# Sheet1.net
KiCad netlist of a schematic drawn in Altium Designer
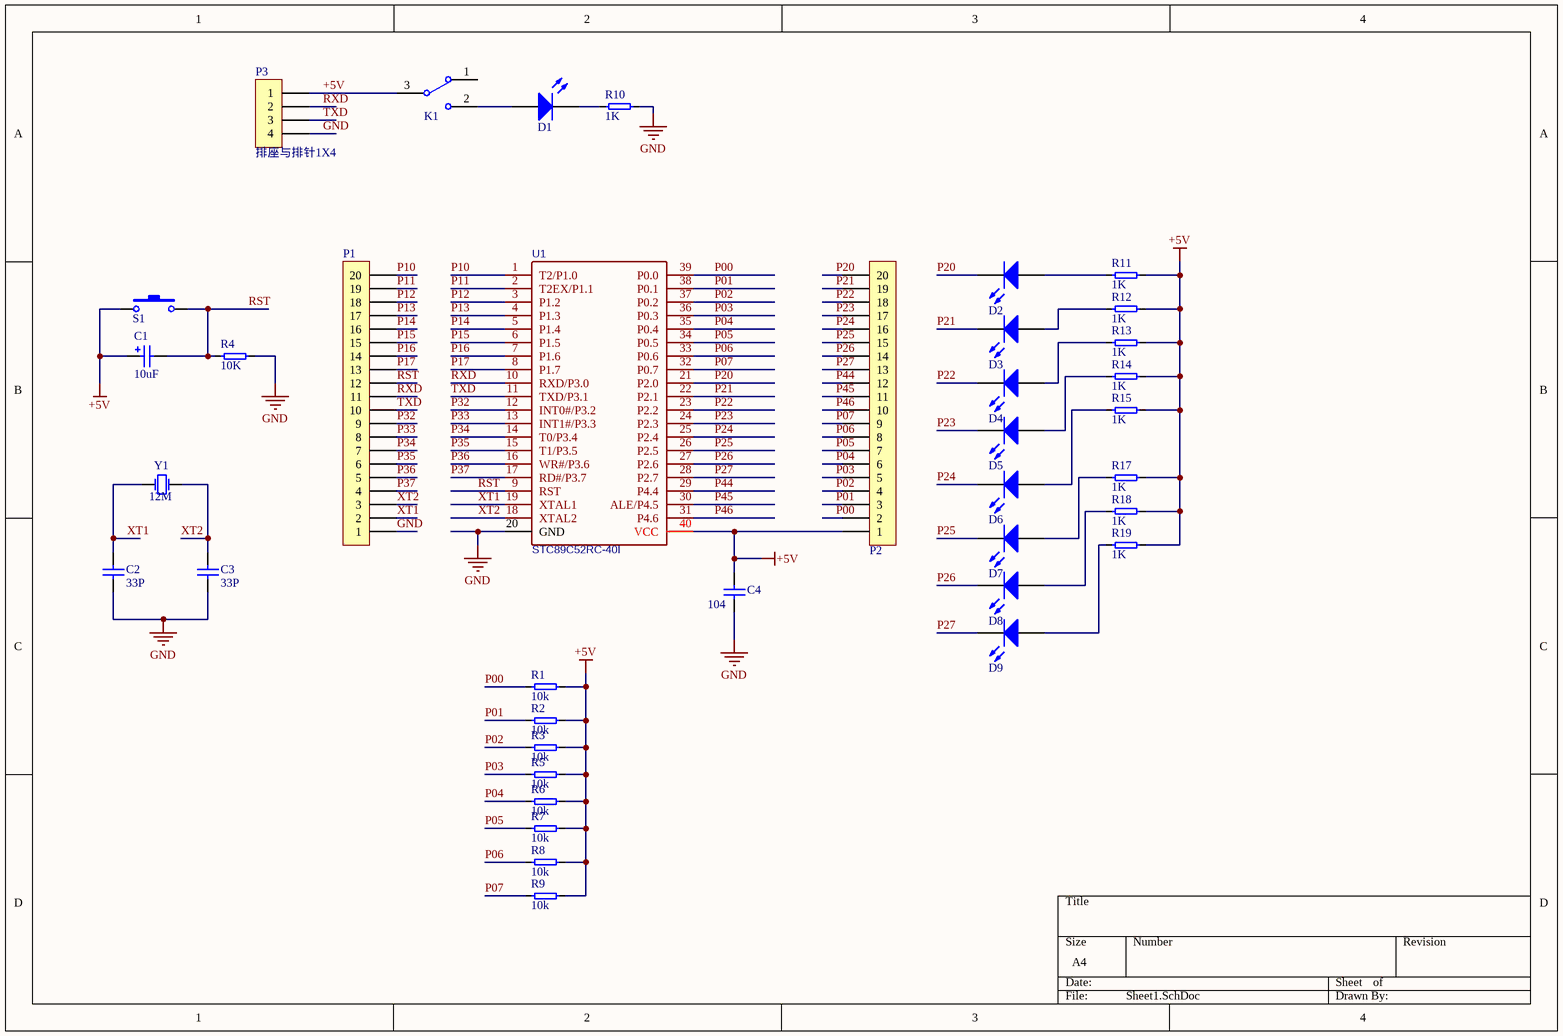
[diagram p0: Sheet1.SchDoc]

(export (version "E")
  (design (tool "Eeschema 10.0.6"))
  (components
    (comp (ref "C1") (value "10uF") (footprint "CAP4*7") (libsource (lib "Csust_B503") (part "电解电容")))
    (comp (ref "C2") (value "33P") (footprint "0805-C") (libsource (lib "Csust_B503") (part "电容")))
    (comp (ref "C3") (value "33P") (footprint "0805-C") (libsource (lib "Csust_B503") (part "电容")))
    (comp (ref "C4") (value "104") (footprint "0805-C") (libsource (lib "Csust_B503") (part "电容")))
    (comp (ref "D1") (value "LED") (footprint "LED-BLUE-0805") (libsource (lib "Csust_B503") (part "LED")))
    (comp (ref "D2") (value "LED") (footprint "LED-BLUE-0805") (libsource (lib "Csust_B503") (part "LED")))
    (comp (ref "D3") (value "LED") (footprint "LED-BLUE-0805") (libsource (lib "Csust_B503") (part "LED")))
    (comp (ref "D4") (value "LED") (footprint "LED-BLUE-0805") (libsource (lib "Csust_B503") (part "LED")))
    (comp (ref "D5") (value "LED") (footprint "LED-BLUE-0805") (libsource (lib "Csust_B503") (part "LED")))
    (comp (ref "D6") (value "LED") (footprint "LED-BLUE-0805") (libsource (lib "Csust_B503") (part "LED")))
    (comp (ref "D7") (value "LED") (footprint "LED-BLUE-0805") (libsource (lib "Csust_B503") (part "LED")))
    (comp (ref "D8") (value "LED") (footprint "LED-BLUE-0805") (libsource (lib "Csust_B503") (part "LED")))
    (comp (ref "D9") (value "LED") (footprint "LED-BLUE-0805") (libsource (lib "Csust_B503") (part "LED")))
    (comp (ref "K1") (value "开关") (footprint "开关(自锁)") (libsource (lib "Csust_B503") (part "开关")))
    (comp (ref "P1") (value "排座与排针1X20") (footprint "Header1X20") (libsource (lib "") (part "排座与排针1X20_1")))
    (comp (ref "P2")
      (value "排座与排针1X20")
      (footprint "Header1X20")
      (libsource (lib "Csust_B503") (part "排座与排针1X20"))
    )
    (comp (ref "P3")
      (value "排座与排针1X4")
      (footprint "Female1X4")
      (libsource (lib "Csust_B503") (part "排座与排针1X4"))
    )
    (comp (ref "R1") (value "10k") (footprint "0805-R") (libsource (lib "Csust_B503") (part "电阻")))
    (comp (ref "R2") (value "10k") (footprint "0805-R") (libsource (lib "Csust_B503") (part "电阻")))
    (comp (ref "R3") (value "10k") (footprint "0805-R") (libsource (lib "Csust_B503") (part "电阻")))
    (comp (ref "R4") (value "10K") (footprint "0805-R") (libsource (lib "Csust_B503") (part "电阻")))
    (comp (ref "R5") (value "10k") (footprint "0805-R") (libsource (lib "Csust_B503") (part "电阻")))
    (comp (ref "R6") (value "10k") (footprint "0805-R") (libsource (lib "Csust_B503") (part "电阻")))
    (comp (ref "R7") (value "10k") (footprint "0805-R") (libsource (lib "Csust_B503") (part "电阻")))
    (comp (ref "R8") (value "10k") (footprint "0805-R") (libsource (lib "Csust_B503") (part "电阻")))
    (comp (ref "R9") (value "10k") (footprint "0805-R") (libsource (lib "Csust_B503") (part "电阻")))
    (comp (ref "R10") (value "1K") (footprint "0805-R") (libsource (lib "Csust_B503") (part "电阻")))
    (comp (ref "R11") (value "1K") (footprint "0805-R") (libsource (lib "Csust_B503") (part "电阻")))
    (comp (ref "R12") (value "1K") (footprint "0805-R") (libsource (lib "Csust_B503") (part "电阻")))
    (comp (ref "R13") (value "1K") (footprint "0805-R") (libsource (lib "Csust_B503") (part "电阻")))
    (comp (ref "R14") (value "1K") (footprint "0805-R") (libsource (lib "Csust_B503") (part "电阻")))
    (comp (ref "R15") (value "1K") (footprint "0805-R") (libsource (lib "Csust_B503") (part "电阻")))
    (comp (ref "R17") (value "1K") (footprint "0805-R") (libsource (lib "Csust_B503") (part "电阻")))
    (comp (ref "R18") (value "1K") (footprint "0805-R") (libsource (lib "Csust_B503") (part "电阻")))
    (comp (ref "R19") (value "1K") (footprint "0805-R") (libsource (lib "Csust_B503") (part "电阻")))
    (comp (ref "S1") (value "按键") (footprint "按键(小)") (libsource (lib "Csust_B503") (part "按键")))
    (comp (ref "U1")
      (value "STC89C52RC-40I")
      (footprint "DIP-40_LS15.24-L52.58-W13.97-H4.83-PITCH2.54")
      (fields (field (name "BOM_SUPPLIER PART") "C14022"))
      (libsource (lib "MUAT") (part "STC89C52RC-40I"))
    )
    (comp (ref "Y1") (value "12M") (footprint "晶振(HC49S型)") (libsource (lib "Csust_B503") (part "晶振")))
  )
  (nets
    (net (code "1") (name "+5V") (class "Default")
      (node (ref "C1") (pin "1") (pinfunction "1_1") (pintype "passive"))
      (node (ref "C4") (pin "2") (pinfunction "2_2") (pintype "power_in"))
      (node (ref "K1") (pin "3") (pinfunction "3_3") (pintype "passive"))
      (node (ref "P2") (pin "1") (pinfunction "1_1") (pintype "passive"))
      (node (ref "P3") (pin "1") (pinfunction "1_1") (pintype "passive"))
      (node (ref "R1") (pin "2") (pinfunction "2_2") (pintype "passive"))
      (node (ref "R11") (pin "2") (pinfunction "2_2") (pintype "passive"))
      (node (ref "R12") (pin "2") (pinfunction "2_2") (pintype "passive"))
      (node (ref "R13") (pin "2") (pinfunction "2_2") (pintype "passive"))
      (node (ref "R14") (pin "2") (pinfunction "2_2") (pintype "passive"))
      (node (ref "R15") (pin "2") (pinfunction "2_2") (pintype "passive"))
      (node (ref "R17") (pin "2") (pinfunction "2_2") (pintype "passive"))
      (node (ref "R18") (pin "2") (pinfunction "2_2") (pintype "passive"))
      (node (ref "R19") (pin "2") (pinfunction "2_2") (pintype "passive"))
      (node (ref "R2") (pin "2") (pinfunction "2_2") (pintype "passive"))
      (node (ref "R3") (pin "2") (pinfunction "2_2") (pintype "passive"))
      (node (ref "R5") (pin "2") (pinfunction "2_2") (pintype "passive"))
      (node (ref "R6") (pin "2") (pinfunction "2_2") (pintype "passive"))
      (node (ref "R7") (pin "2") (pinfunction "2_2") (pintype "passive"))
      (node (ref "R8") (pin "2") (pinfunction "2_2") (pintype "passive"))
      (node (ref "R9") (pin "2") (pinfunction "2_2") (pintype "passive"))
      (node (ref "S1") (pin "1") (pinfunction "1_1") (pintype "passive"))
      (node (ref "U1") (pin "40") (pinfunction "VCC_40") (pintype "passive"))
    )
    (net (code "2") (name "/P00") (class "Default")
      (node (ref "P2") (pin "2") (pinfunction "2_2") (pintype "passive"))
      (node (ref "R1") (pin "1") (pinfunction "1_1") (pintype "passive"))
      (node (ref "U1") (pin "39") (pinfunction "P0.0_39") (pintype "passive"))
    )
    (net (code "3") (name "/P01") (class "Default")
      (node (ref "P2") (pin "3") (pinfunction "3_3") (pintype "passive"))
      (node (ref "R2") (pin "1") (pinfunction "1_1") (pintype "passive"))
      (node (ref "U1") (pin "38") (pinfunction "P0.1_38") (pintype "passive"))
    )
    (net (code "4") (name "/P02") (class "Default")
      (node (ref "P2") (pin "4") (pinfunction "4_4") (pintype "passive"))
      (node (ref "R3") (pin "1") (pinfunction "1_1") (pintype "passive"))
      (node (ref "U1") (pin "37") (pinfunction "P0.2_37") (pintype "passive"))
    )
    (net (code "5") (name "/P03") (class "Default")
      (node (ref "P2") (pin "5") (pinfunction "5_5") (pintype "passive"))
      (node (ref "R5") (pin "1") (pinfunction "1_1") (pintype "passive"))
      (node (ref "U1") (pin "36") (pinfunction "P0.3_36") (pintype "passive"))
    )
    (net (code "6") (name "/P04") (class "Default")
      (node (ref "P2") (pin "6") (pinfunction "6_6") (pintype "passive"))
      (node (ref "R6") (pin "1") (pinfunction "1_1") (pintype "passive"))
      (node (ref "U1") (pin "35") (pinfunction "P0.4_35") (pintype "passive"))
    )
    (net (code "7") (name "/P05") (class "Default")
      (node (ref "P2") (pin "7") (pinfunction "7_7") (pintype "passive"))
      (node (ref "R7") (pin "1") (pinfunction "1_1") (pintype "passive"))
      (node (ref "U1") (pin "34") (pinfunction "P0.5_34") (pintype "passive"))
    )
    (net (code "8") (name "/P06") (class "Default")
      (node (ref "P2") (pin "8") (pinfunction "8_8") (pintype "passive"))
      (node (ref "R8") (pin "1") (pinfunction "1_1") (pintype "passive"))
      (node (ref "U1") (pin "33") (pinfunction "P0.6_33") (pintype "passive"))
    )
    (net (code "9") (name "/P07") (class "Default")
      (node (ref "P2") (pin "9") (pinfunction "9_9") (pintype "passive"))
      (node (ref "R9") (pin "1") (pinfunction "1_1") (pintype "passive"))
      (node (ref "U1") (pin "32") (pinfunction "P0.7_32") (pintype "passive"))
    )
    (net (code "10") (name "/P10") (class "Default")
      (node (ref "P1") (pin "20") (pinfunction "20_20") (pintype "passive"))
      (node (ref "U1") (pin "1") (pinfunction "T2/P1.0_1") (pintype "passive"))
    )
    (net (code "11") (name "/P11") (class "Default")
      (node (ref "P1") (pin "19") (pinfunction "19_19") (pintype "passive"))
      (node (ref "U1") (pin "2") (pinfunction "T2EX/P1.1_2") (pintype "passive"))
    )
    (net (code "12") (name "/P12") (class "Default")
      (node (ref "P1") (pin "18") (pinfunction "18_18") (pintype "passive"))
      (node (ref "U1") (pin "3") (pinfunction "P1.2_3") (pintype "passive"))
    )
    (net (code "13") (name "/P13") (class "Default")
      (node (ref "P1") (pin "17") (pinfunction "17_17") (pintype "passive"))
      (node (ref "U1") (pin "4") (pinfunction "P1.3_4") (pintype "passive"))
    )
    (net (code "14") (name "/P14") (class "Default")
      (node (ref "P1") (pin "16") (pinfunction "16_16") (pintype "passive"))
      (node (ref "U1") (pin "5") (pinfunction "P1.4_5") (pintype "passive"))
    )
    (net (code "15") (name "/P15") (class "Default")
      (node (ref "P1") (pin "15") (pinfunction "15_15") (pintype "passive"))
      (node (ref "U1") (pin "6") (pinfunction "P1.5_6") (pintype "passive"))
    )
    (net (code "16") (name "/P16") (class "Default")
      (node (ref "P1") (pin "14") (pinfunction "14_14") (pintype "passive"))
      (node (ref "U1") (pin "7") (pinfunction "P1.6_7") (pintype "passive"))
    )
    (net (code "17") (name "/P17") (class "Default")
      (node (ref "P1") (pin "13") (pinfunction "13_13") (pintype "passive"))
      (node (ref "U1") (pin "8") (pinfunction "P1.7_8") (pintype "passive"))
    )
    (net (code "18") (name "/P20") (class "Default")
      (node (ref "D2") (pin "2") (pinfunction "K_2") (pintype "passive"))
      (node (ref "P2") (pin "20") (pinfunction "20_20") (pintype "passive"))
      (node (ref "U1") (pin "21") (pinfunction "P2.0_21") (pintype "passive"))
    )
    (net (code "19") (name "/P21") (class "Default")
      (node (ref "D3") (pin "2") (pinfunction "K_2") (pintype "passive"))
      (node (ref "P2") (pin "19") (pinfunction "19_19") (pintype "passive"))
      (node (ref "U1") (pin "22") (pinfunction "P2.1_22") (pintype "passive"))
    )
    (net (code "20") (name "/P22") (class "Default")
      (node (ref "D4") (pin "2") (pinfunction "K_2") (pintype "passive"))
      (node (ref "P2") (pin "18") (pinfunction "18_18") (pintype "passive"))
      (node (ref "U1") (pin "23") (pinfunction "P2.2_23") (pintype "passive"))
    )
    (net (code "21") (name "/P23") (class "Default")
      (node (ref "D5") (pin "2") (pinfunction "K_2") (pintype "passive"))
      (node (ref "P2") (pin "17") (pinfunction "17_17") (pintype "passive"))
      (node (ref "U1") (pin "24") (pinfunction "P2.3_24") (pintype "passive"))
    )
    (net (code "22") (name "/P24") (class "Default")
      (node (ref "D6") (pin "2") (pinfunction "K_2") (pintype "passive"))
      (node (ref "P2") (pin "16") (pinfunction "16_16") (pintype "passive"))
      (node (ref "U1") (pin "25") (pinfunction "P2.4_25") (pintype "passive"))
    )
    (net (code "23") (name "/P25") (class "Default")
      (node (ref "D7") (pin "2") (pinfunction "K_2") (pintype "passive"))
      (node (ref "P2") (pin "15") (pinfunction "15_15") (pintype "passive"))
      (node (ref "U1") (pin "26") (pinfunction "P2.5_26") (pintype "passive"))
    )
    (net (code "24") (name "/P26") (class "Default")
      (node (ref "D8") (pin "2") (pinfunction "K_2") (pintype "passive"))
      (node (ref "P2") (pin "14") (pinfunction "14_14") (pintype "passive"))
      (node (ref "U1") (pin "27") (pinfunction "P2.6_27") (pintype "passive"))
    )
    (net (code "25") (name "/P27") (class "Default")
      (node (ref "D9") (pin "2") (pinfunction "K_2") (pintype "passive"))
      (node (ref "P2") (pin "13") (pinfunction "13_13") (pintype "passive"))
      (node (ref "U1") (pin "28") (pinfunction "P2.7_28") (pintype "passive"))
    )
    (net (code "26") (name "/P32") (class "Default")
      (node (ref "P1") (pin "9") (pinfunction "9_9") (pintype "passive"))
      (node (ref "U1") (pin "12") (pinfunction "INT0#/P3.2_12") (pintype "passive"))
    )
    (net (code "27") (name "/P33") (class "Default")
      (node (ref "P1") (pin "8") (pinfunction "8_8") (pintype "passive"))
      (node (ref "U1") (pin "13") (pinfunction "INT1#/P3.3_13") (pintype "passive"))
    )
    (net (code "28") (name "/P34") (class "Default")
      (node (ref "P1") (pin "7") (pinfunction "7_7") (pintype "passive"))
      (node (ref "U1") (pin "14") (pinfunction "T0/P3.4_14") (pintype "passive"))
    )
    (net (code "29") (name "/P35") (class "Default")
      (node (ref "P1") (pin "6") (pinfunction "6_6") (pintype "passive"))
      (node (ref "U1") (pin "15") (pinfunction "T1/P3.5_15") (pintype "passive"))
    )
    (net (code "30") (name "/P36") (class "Default")
      (node (ref "P1") (pin "5") (pinfunction "5_5") (pintype "passive"))
      (node (ref "U1") (pin "16") (pinfunction "WR#/P3.6_16") (pintype "passive"))
    )
    (net (code "31") (name "/P37") (class "Default")
      (node (ref "P1") (pin "4") (pinfunction "4_4") (pintype "passive"))
      (node (ref "U1") (pin "17") (pinfunction "RD#/P3.7_17") (pintype "passive"))
    )
    (net (code "32") (name "/P44") (class "Default")
      (node (ref "P2") (pin "12") (pinfunction "12_12") (pintype "passive"))
      (node (ref "U1") (pin "29") (pinfunction "P4.4_29") (pintype "passive"))
    )
    (net (code "33") (name "/P45") (class "Default")
      (node (ref "P2") (pin "11") (pinfunction "11_11") (pintype "passive"))
      (node (ref "U1") (pin "30") (pinfunction "ALE/P4.5_30") (pintype "passive"))
    )
    (net (code "34") (name "/P46") (class "Default")
      (node (ref "P2") (pin "10") (pinfunction "10_10") (pintype "passive"))
      (node (ref "U1") (pin "31") (pinfunction "P4.6_31") (pintype "passive"))
    )
    (net (code "35") (name "/RST") (class "Default")
      (node (ref "C1") (pin "2") (pinfunction "2_2") (pintype "passive"))
      (node (ref "P1") (pin "12") (pinfunction "12_12") (pintype "passive"))
      (node (ref "R4") (pin "1") (pinfunction "1_1") (pintype "passive"))
      (node (ref "S1") (pin "2") (pinfunction "2_2") (pintype "passive"))
      (node (ref "U1") (pin "9") (pinfunction "RST_9") (pintype "passive"))
    )
    (net (code "36") (name "/RXD") (class "Default")
      (node (ref "P1") (pin "11") (pinfunction "11_11") (pintype "passive"))
      (node (ref "P3") (pin "2") (pinfunction "2_2") (pintype "passive"))
      (node (ref "U1") (pin "10") (pinfunction "RXD/P3.0_10") (pintype "passive"))
    )
    (net (code "37") (name "/TXD") (class "Default")
      (node (ref "P1") (pin "10") (pinfunction "10_10") (pintype "passive"))
      (node (ref "P3") (pin "3") (pinfunction "3_3") (pintype "passive"))
      (node (ref "U1") (pin "11") (pinfunction "TXD/P3.1_11") (pintype "passive"))
    )
    (net (code "38") (name "/XT1") (class "Default")
      (node (ref "C2") (pin "2") (pinfunction "2_2") (pintype "power_in"))
      (node (ref "P1") (pin "2") (pinfunction "2_2") (pintype "passive"))
      (node (ref "U1") (pin "19") (pinfunction "XTAL1_19") (pintype "passive"))
      (node (ref "Y1") (pin "1") (pinfunction "OSC1_1") (pintype "passive"))
    )
    (net (code "39") (name "/XT2") (class "Default")
      (node (ref "C3") (pin "2") (pinfunction "2_2") (pintype "power_in"))
      (node (ref "P1") (pin "3") (pinfunction "3_3") (pintype "passive"))
      (node (ref "U1") (pin "18") (pinfunction "XTAL2_18") (pintype "passive"))
      (node (ref "Y1") (pin "2") (pinfunction "OSC2_2") (pintype "passive"))
    )
    (net (code "40") (name "GND") (class "Default")
      (node (ref "C2") (pin "1") (pinfunction "1_1") (pintype "passive"))
      (node (ref "C3") (pin "1") (pinfunction "1_1") (pintype "passive"))
      (node (ref "C4") (pin "1") (pinfunction "1_1") (pintype "passive"))
      (node (ref "P1") (pin "1") (pinfunction "1_1") (pintype "passive"))
      (node (ref "P3") (pin "4") (pinfunction "4_4") (pintype "passive"))
      (node (ref "R10") (pin "2") (pinfunction "2_2") (pintype "passive"))
      (node (ref "R4") (pin "2") (pinfunction "2_2") (pintype "passive"))
      (node (ref "U1") (pin "20") (pinfunction "GND_20") (pintype "passive"))
    )
    (net (code "41") (name "Net-(D1-A)") (class "Default")
      (node (ref "D1") (pin "1") (pinfunction "A_1") (pintype "passive"))
      (node (ref "K1") (pin "2") (pinfunction "2_2") (pintype "passive"))
    )
    (net (code "42") (name "Net-(D1-K)") (class "Default")
      (node (ref "D1") (pin "2") (pinfunction "K_2") (pintype "passive"))
      (node (ref "R10") (pin "1") (pinfunction "1_1") (pintype "passive"))
    )
    (net (code "43") (name "Net-(D2-A)") (class "Default")
      (node (ref "D2") (pin "1") (pinfunction "A_1") (pintype "passive"))
      (node (ref "R11") (pin "1") (pinfunction "1_1") (pintype "passive"))
    )
    (net (code "44") (name "Net-(D3-A)") (class "Default")
      (node (ref "D3") (pin "1") (pinfunction "A_1") (pintype "passive"))
      (node (ref "R12") (pin "1") (pinfunction "1_1") (pintype "passive"))
    )
    (net (code "45") (name "Net-(D4-A)") (class "Default")
      (node (ref "D4") (pin "1") (pinfunction "A_1") (pintype "passive"))
      (node (ref "R13") (pin "1") (pinfunction "1_1") (pintype "passive"))
    )
    (net (code "46") (name "Net-(D5-A)") (class "Default")
      (node (ref "D5") (pin "1") (pinfunction "A_1") (pintype "passive"))
      (node (ref "R14") (pin "1") (pinfunction "1_1") (pintype "passive"))
    )
    (net (code "47") (name "Net-(D6-A)") (class "Default")
      (node (ref "D6") (pin "1") (pinfunction "A_1") (pintype "passive"))
      (node (ref "R15") (pin "1") (pinfunction "1_1") (pintype "passive"))
    )
    (net (code "48") (name "Net-(D7-A)") (class "Default")
      (node (ref "D7") (pin "1") (pinfunction "A_1") (pintype "passive"))
      (node (ref "R17") (pin "1") (pinfunction "1_1") (pintype "passive"))
    )
    (net (code "49") (name "Net-(D8-A)") (class "Default")
      (node (ref "D8") (pin "1") (pinfunction "A_1") (pintype "passive"))
      (node (ref "R18") (pin "1") (pinfunction "1_1") (pintype "passive"))
    )
    (net (code "50") (name "Net-(D9-A)") (class "Default")
      (node (ref "D9") (pin "1") (pinfunction "A_1") (pintype "passive"))
      (node (ref "R19") (pin "1") (pinfunction "1_1") (pintype "passive"))
    )
    (net (code "51") (name "unconnected-(K1-Pad1)") (class "Default")
      (node (ref "K1") (pin "1") (pinfunction "1_1") (pintype "passive"))
    )
  )
)
